# Boost.net
KiCad netlist of a schematic drawn in Altium Designer
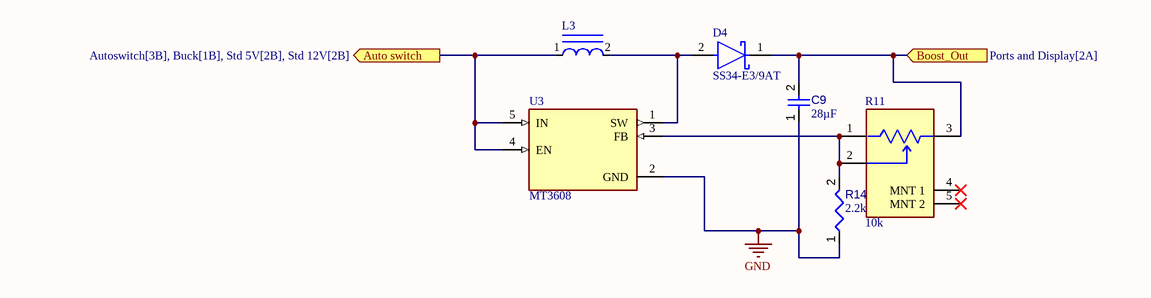
[diagram p0: Boost.SchDoc]

(export (version "E")
  (design (tool "Eeschema 10.0.6"))
  (components
    (comp (ref "C9")
      (value "28µF")
      (footprint "CAPC0805(2012)145_L")
      (description "Chip Capacitor, 47µF +/-40%, 6.3V, 0805, Thickness 1.45 mm")
      (fields (field (name "TOLERANCE") "10%") (field (name "Comment") "Capacitor 47µF +/-40% 6.3V 0805"))
      (libsource (lib "Vedant Ashtankar") (part "CAP-NP-2"))
    )
    (comp (ref "D4")
      (value "SS34-E3/9AT")
      (footprint "FP-SMC-MFG")
      (description "Rectifier Diode, Schottky, 1 Phase, 1 Element, 3A, 40V V(RRM), Silicon, DO-214AB")
      (libsource (lib "Vedant Ashtankar") (part "c1678fac7984e62e0809fbf79c06691"))
    )
    (comp (ref "L3")
      (value "DR127-330-R")
      (footprint "FP-DR127-MFG")
      (description "General Purpose Inductor, 33uH, 20%, 1 Element, Ferrite-Core, SMD, 4949")
      (fields (field (name "TOLERANCE") "20%"))
      (libsource (lib "Vedant Ashtankar") (part "595efa879b4242f50b2b19a2702faec"))
    )
    (comp (ref "R11")
      (value "10k")
      (footprint "FP-PTV09A-4-MFG")
      (description "Potentiometer, Carbon, 0.05W, 10000ohm, 20V, 20% +/-Tol, 3943")
      (fields (field (name "TOLERANCE") "20%") (field (name "POWER") "50mW"))
      (libsource (lib "Vedant Ashtankar") (part "705d11b747745a787204d796a5f3d12"))
    )
    (comp (ref "R14")
      (value "2.2k")
      (footprint "RESC0805(2012)_L")
      (description "1K 0.125W 5% 0805 (2012 Metric)  SMD")
      (fields (field (name "TOLERANCE") "5%") (field (name "POWER") "125mW"))
      (libsource (lib "Vedant Ashtankar") (part "1KR5J"))
    )
    (comp (ref "U3")
      (value "MT3608")
      (footprint "SOT95P280X145-6N")
      (description "High Efficiency 1.2MHz2A Step Up Converter")
      (fields (field (name "MF") "Aerosemi Technology Co., Ltd"))
      (libsource (lib "Vedant Ashtankar") (part "MT3608"))
    )
  )
  (nets
    (net (code "1") (name "/Auto switch") (class "Default")
      (node (ref "L3") (pin "1") (pinfunction "1_1") (pintype "passive"))
      (node (ref "U3") (pin "4") (pinfunction "EN_4") (pintype "input"))
      (node (ref "U3") (pin "5") (pinfunction "IN_5") (pintype "input"))
    )
    (net (code "2") (name "/Boost_Out") (class "Default")
      (node (ref "C9") (pin "2") (pinfunction "2_2") (pintype "passive"))
      (node (ref "D4") (pin "1") (pinfunction "C_1") (pintype "passive"))
      (node (ref "R11") (pin "3") (pinfunction "3_3") (pintype "passive"))
    )
    (net (code "3") (name "GND") (class "Default")
      (node (ref "C9") (pin "1") (pinfunction "1_1") (pintype "passive"))
      (node (ref "R14") (pin "1") (pinfunction "1_1") (pintype "passive"))
      (node (ref "U3") (pin "2") (pinfunction "GND_2") (pintype "power_in"))
    )
    (net (code "4") (name "Net-(D4-A)") (class "Default")
      (node (ref "D4") (pin "2") (pinfunction "A_2") (pintype "passive"))
      (node (ref "L3") (pin "2") (pinfunction "2_2") (pintype "passive"))
      (node (ref "U3") (pin "1") (pinfunction "SW_1") (pintype "output"))
    )
    (net (code "5") (name "Net-(U3-FB)") (class "Default")
      (node (ref "R11") (pin "1") (pinfunction "1_1") (pintype "passive"))
      (node (ref "R11") (pin "2") (pinfunction "2_2") (pintype "passive"))
      (node (ref "R14") (pin "2") (pinfunction "2_2") (pintype "passive"))
      (node (ref "U3") (pin "3") (pinfunction "FB_3") (pintype "input"))
    )
    (net (code "6") (name "unconnected-(R11-MNT_1-Pad4)") (class "Default")
      (node (ref "R11") (pin "4") (pinfunction "MNT_1_4") (pintype "passive+no_connect"))
    )
    (net (code "7") (name "unconnected-(R11-MNT_2-Pad5)") (class "Default")
      (node (ref "R11") (pin "5") (pinfunction "MNT_2_5") (pintype "passive+no_connect"))
    )
  )
)
